# VoltageLevelMeter3.net
KiCad netlist of a schematic drawn in EAGLE
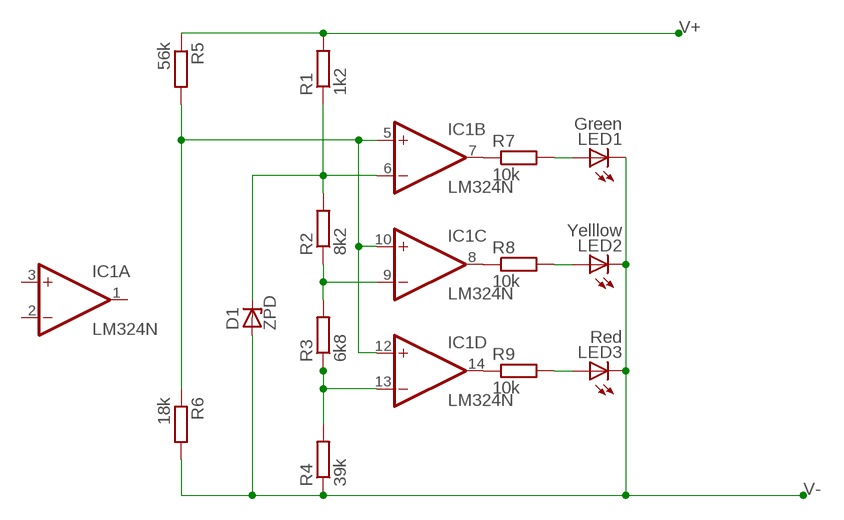
[diagram p0: schematic, sheet 1]

(export (version "E")
  (design (tool "Eeschema 10.0.6"))
  (components
    (comp (ref "D1")
      (value "ZPD")
      (footprint "eagle-import:DO35Z10")
      (libsource (lib "eagle-import") (part "ZPD"))
    )
    (comp (ref "IC1")
      (value "LM324N")
      (footprint "eagle-import:DIL14")
      (libsource (lib "eagle-import") (part "LM324N"))
    )
    (comp (ref "LED1")
      (value "Green")
      (footprint "eagle-import:LED3MM")
      (libsource (lib "eagle-import") (part "LED3MM"))
    )
    (comp (ref "LED2")
      (value "Yelllow")
      (footprint "eagle-import:LED3MM")
      (libsource (lib "eagle-import") (part "LED3MM"))
    )
    (comp (ref "LED3")
      (value "Red")
      (footprint "eagle-import:LED3MM")
      (libsource (lib "eagle-import") (part "LED3MM"))
    )
    (comp (ref "R1")
      (value "1k2")
      (footprint "eagle-import:0207_7")
      (libsource (lib "eagle-import") (part "R-EU_0207/7"))
    )
    (comp (ref "R2")
      (value "8k2")
      (footprint "eagle-import:0207_7")
      (libsource (lib "eagle-import") (part "R-EU_0207/7"))
    )
    (comp (ref "R3")
      (value "6k8")
      (footprint "eagle-import:0207_7")
      (libsource (lib "eagle-import") (part "R-EU_0207/7"))
    )
    (comp (ref "R4")
      (value "39k")
      (footprint "eagle-import:0207_7")
      (libsource (lib "eagle-import") (part "R-EU_0207/7"))
    )
    (comp (ref "R5")
      (value "56k")
      (footprint "eagle-import:0207_7")
      (libsource (lib "eagle-import") (part "R-EU_0207/7"))
    )
    (comp (ref "R6")
      (value "18k")
      (footprint "eagle-import:0207_7")
      (libsource (lib "eagle-import") (part "R-EU_0207/7"))
    )
    (comp (ref "R7")
      (value "10k")
      (footprint "eagle-import:0207_7")
      (libsource (lib "eagle-import") (part "R-EU_0207/7"))
    )
    (comp (ref "R8")
      (value "10k")
      (footprint "eagle-import:0207_7")
      (libsource (lib "eagle-import") (part "R-EU_0207/7"))
    )
    (comp (ref "R9")
      (value "10k")
      (footprint "eagle-import:0207_7")
      (libsource (lib "eagle-import") (part "R-EU_0207/7"))
    )
  )
  (nets
    (net (code "1") (name "/V+") (class "Default")
      (node (ref "R1") (pin "2") (pinfunction "2_2") (pintype "passive"))
      (node (ref "R5") (pin "1") (pinfunction "1_1") (pintype "passive"))
    )
    (net (code "2") (name "/V-") (class "Default")
      (node (ref "D1") (pin "A") (pinfunction "A_A") (pintype "passive"))
      (node (ref "LED1") (pin "K") (pinfunction "C_K") (pintype "passive"))
      (node (ref "LED2") (pin "K") (pinfunction "C_K") (pintype "passive"))
      (node (ref "LED3") (pin "K") (pinfunction "C_K") (pintype "passive"))
      (node (ref "R4") (pin "1") (pinfunction "1_1") (pintype "passive"))
      (node (ref "R6") (pin "2") (pinfunction "2_2") (pintype "passive"))
    )
    (net (code "3") (name "Net-(IC1B-+IN)") (class "Default")
      (node (ref "IC1") (pin "10") (pinfunction "+IN_10") (pintype "input"))
      (node (ref "IC1") (pin "12") (pinfunction "+IN_12") (pintype "input"))
      (node (ref "IC1") (pin "5") (pinfunction "+IN_5") (pintype "input"))
      (node (ref "R5") (pin "2") (pinfunction "2_2") (pintype "passive"))
      (node (ref "R6") (pin "1") (pinfunction "1_1") (pintype "passive"))
    )
    (net (code "4") (name "Net-(IC1B--IN)") (class "Default")
      (node (ref "D1") (pin "C") (pinfunction "C_C") (pintype "passive"))
      (node (ref "IC1") (pin "6") (pinfunction "-IN_6") (pintype "input"))
      (node (ref "R1") (pin "1") (pinfunction "1_1") (pintype "passive"))
      (node (ref "R2") (pin "2") (pinfunction "2_2") (pintype "passive"))
    )
    (net (code "5") (name "Net-(IC1B-OUT)") (class "Default")
      (node (ref "IC1") (pin "7") (pinfunction "OUT_7") (pintype "output"))
      (node (ref "R7") (pin "1") (pinfunction "1_1") (pintype "passive"))
    )
    (net (code "6") (name "Net-(IC1C--IN)") (class "Default")
      (node (ref "IC1") (pin "9") (pinfunction "-IN_9") (pintype "input"))
      (node (ref "R2") (pin "1") (pinfunction "1_1") (pintype "passive"))
      (node (ref "R3") (pin "2") (pinfunction "2_2") (pintype "passive"))
    )
    (net (code "7") (name "Net-(IC1C-OUT)") (class "Default")
      (node (ref "IC1") (pin "8") (pinfunction "OUT_8") (pintype "output"))
      (node (ref "R8") (pin "1") (pinfunction "1_1") (pintype "passive"))
    )
    (net (code "8") (name "Net-(IC1D--IN)") (class "Default")
      (node (ref "IC1") (pin "13") (pinfunction "-IN_13") (pintype "input"))
      (node (ref "R3") (pin "1") (pinfunction "1_1") (pintype "passive"))
      (node (ref "R4") (pin "2") (pinfunction "2_2") (pintype "passive"))
    )
    (net (code "9") (name "Net-(IC1D-OUT)") (class "Default")
      (node (ref "IC1") (pin "14") (pinfunction "OUT_14") (pintype "output"))
      (node (ref "R9") (pin "1") (pinfunction "1_1") (pintype "passive"))
    )
    (net (code "10") (name "Net-(LED1-PadA)") (class "Default")
      (node (ref "LED1") (pin "A") (pinfunction "A_A") (pintype "passive"))
      (node (ref "R7") (pin "2") (pinfunction "2_2") (pintype "passive"))
    )
    (net (code "11") (name "Net-(LED2-PadA)") (class "Default")
      (node (ref "LED2") (pin "A") (pinfunction "A_A") (pintype "passive"))
      (node (ref "R8") (pin "2") (pinfunction "2_2") (pintype "passive"))
    )
    (net (code "12") (name "Net-(LED3-PadA)") (class "Default")
      (node (ref "LED3") (pin "A") (pinfunction "A_A") (pintype "passive"))
      (node (ref "R9") (pin "2") (pinfunction "2_2") (pintype "passive"))
    )
    (net (code "13") (name "unconnected-(IC1A-+IN-Pad3)") (class "Default")
      (node (ref "IC1") (pin "3") (pinfunction "+IN_3") (pintype "input"))
    )
    (net (code "14") (name "unconnected-(IC1A--IN-Pad2)") (class "Default")
      (node (ref "IC1") (pin "2") (pinfunction "-IN_2") (pintype "input"))
    )
    (net (code "15") (name "unconnected-(IC1A-OUT-Pad1)") (class "Default")
      (node (ref "IC1") (pin "1") (pinfunction "OUT_1") (pintype "output"))
    )
  )
)
